# TEST_PLATFORM.net
KiCad netlist of a schematic drawn in Altium Designer
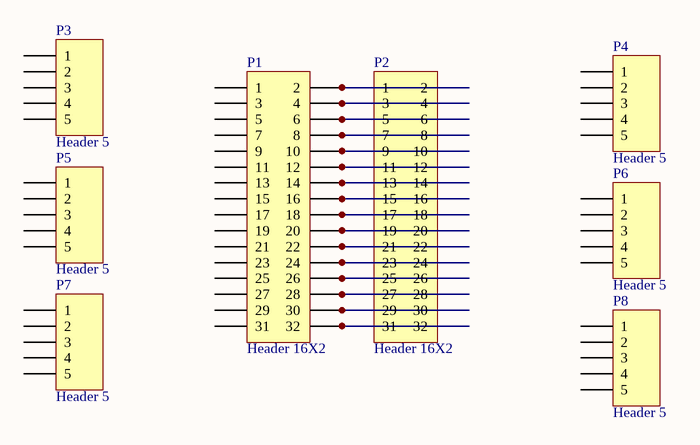
[diagram p0: TEST_PLATFORM.SchDoc]

(export (version "E")
  (design (tool "Eeschema 10.0.6"))
  (components
    (comp (ref "P1")
      (value "Header 16X2")
      (footprint "HDR2X16")
      (description "Header, 16-Pin, Dual row")
      (fields (field (name "PUBLISHER") "Altium Limited"))
      (libsource (lib "Miscellaneous Connectors") (part "Header 16X2"))
    )
    (comp (ref "P2")
      (value "Header 16X2")
      (footprint "HDR2X16")
      (description "Header, 16-Pin, Dual row")
      (fields (field (name "PUBLISHER") "Altium Limited"))
      (libsource (lib "Miscellaneous Connectors") (part "Header 16X2"))
    )
    (comp (ref "P3")
      (value "Header 5")
      (footprint "HDR1X5")
      (description "Header, 5-Pin")
      (fields (field (name "PUBLISHER") "Altium Limited"))
      (libsource (lib "Miscellaneous Connectors") (part "Header 5"))
    )
    (comp (ref "P4")
      (value "Header 5")
      (footprint "HDR1X5")
      (description "Header, 5-Pin")
      (fields (field (name "PUBLISHER") "Altium Limited"))
      (libsource (lib "Miscellaneous Connectors") (part "Header 5"))
    )
    (comp (ref "P5")
      (value "Header 5")
      (footprint "HDR1X5")
      (description "Header, 5-Pin")
      (fields (field (name "PUBLISHER") "Altium Limited"))
      (libsource (lib "Miscellaneous Connectors") (part "Header 5"))
    )
    (comp (ref "P6")
      (value "Header 5")
      (footprint "HDR1X5")
      (description "Header, 5-Pin")
      (fields (field (name "PUBLISHER") "Altium Limited"))
      (libsource (lib "Miscellaneous Connectors") (part "Header 5"))
    )
    (comp (ref "P7")
      (value "Header 5")
      (footprint "HDR1X5")
      (description "Header, 5-Pin")
      (fields (field (name "PUBLISHER") "Altium Limited"))
      (libsource (lib "Miscellaneous Connectors") (part "Header 5"))
    )
    (comp (ref "P8")
      (value "Header 5")
      (footprint "HDR1X5")
      (description "Header, 5-Pin")
      (fields (field (name "PUBLISHER") "Altium Limited"))
      (libsource (lib "Miscellaneous Connectors") (part "Header 5"))
    )
  )
  (nets
    (net (code "1") (name "Net-(P1-Pad2)") (class "Default")
      (node (ref "P1") (pin "2") (pinfunction "2_2") (pintype "passive"))
      (node (ref "P2") (pin "1") (pinfunction "1_1") (pintype "passive"))
      (node (ref "P2") (pin "2") (pinfunction "2_2") (pintype "passive"))
    )
    (net (code "2") (name "Net-(P1-Pad4)") (class "Default")
      (node (ref "P1") (pin "4") (pinfunction "4_4") (pintype "passive"))
      (node (ref "P2") (pin "3") (pinfunction "3_3") (pintype "passive"))
      (node (ref "P2") (pin "4") (pinfunction "4_4") (pintype "passive"))
    )
    (net (code "3") (name "Net-(P1-Pad6)") (class "Default")
      (node (ref "P1") (pin "6") (pinfunction "6_6") (pintype "passive"))
      (node (ref "P2") (pin "5") (pinfunction "5_5") (pintype "passive"))
      (node (ref "P2") (pin "6") (pinfunction "6_6") (pintype "passive"))
    )
    (net (code "4") (name "Net-(P1-Pad8)") (class "Default")
      (node (ref "P1") (pin "8") (pinfunction "8_8") (pintype "passive"))
      (node (ref "P2") (pin "7") (pinfunction "7_7") (pintype "passive"))
      (node (ref "P2") (pin "8") (pinfunction "8_8") (pintype "passive"))
    )
    (net (code "5") (name "Net-(P1-Pad10)") (class "Default")
      (node (ref "P1") (pin "10") (pinfunction "10_10") (pintype "passive"))
      (node (ref "P2") (pin "10") (pinfunction "10_10") (pintype "passive"))
      (node (ref "P2") (pin "9") (pinfunction "9_9") (pintype "passive"))
    )
    (net (code "6") (name "Net-(P1-Pad12)") (class "Default")
      (node (ref "P1") (pin "12") (pinfunction "12_12") (pintype "passive"))
      (node (ref "P2") (pin "11") (pinfunction "11_11") (pintype "passive"))
      (node (ref "P2") (pin "12") (pinfunction "12_12") (pintype "passive"))
    )
    (net (code "7") (name "Net-(P1-Pad14)") (class "Default")
      (node (ref "P1") (pin "14") (pinfunction "14_14") (pintype "passive"))
      (node (ref "P2") (pin "13") (pinfunction "13_13") (pintype "passive"))
      (node (ref "P2") (pin "14") (pinfunction "14_14") (pintype "passive"))
    )
    (net (code "8") (name "Net-(P1-Pad16)") (class "Default")
      (node (ref "P1") (pin "16") (pinfunction "16_16") (pintype "passive"))
      (node (ref "P2") (pin "15") (pinfunction "15_15") (pintype "passive"))
      (node (ref "P2") (pin "16") (pinfunction "16_16") (pintype "passive"))
    )
    (net (code "9") (name "Net-(P1-Pad18)") (class "Default")
      (node (ref "P1") (pin "18") (pinfunction "18_18") (pintype "passive"))
      (node (ref "P2") (pin "17") (pinfunction "17_17") (pintype "passive"))
      (node (ref "P2") (pin "18") (pinfunction "18_18") (pintype "passive"))
    )
    (net (code "10") (name "Net-(P1-Pad20)") (class "Default")
      (node (ref "P1") (pin "20") (pinfunction "20_20") (pintype "passive"))
      (node (ref "P2") (pin "19") (pinfunction "19_19") (pintype "passive"))
      (node (ref "P2") (pin "20") (pinfunction "20_20") (pintype "passive"))
    )
    (net (code "11") (name "Net-(P1-Pad22)") (class "Default")
      (node (ref "P1") (pin "22") (pinfunction "22_22") (pintype "passive"))
      (node (ref "P2") (pin "21") (pinfunction "21_21") (pintype "passive"))
      (node (ref "P2") (pin "22") (pinfunction "22_22") (pintype "passive"))
    )
    (net (code "12") (name "Net-(P1-Pad24)") (class "Default")
      (node (ref "P1") (pin "24") (pinfunction "24_24") (pintype "passive"))
      (node (ref "P2") (pin "23") (pinfunction "23_23") (pintype "passive"))
      (node (ref "P2") (pin "24") (pinfunction "24_24") (pintype "passive"))
    )
    (net (code "13") (name "Net-(P1-Pad26)") (class "Default")
      (node (ref "P1") (pin "26") (pinfunction "26_26") (pintype "passive"))
      (node (ref "P2") (pin "25") (pinfunction "25_25") (pintype "passive"))
      (node (ref "P2") (pin "26") (pinfunction "26_26") (pintype "passive"))
    )
    (net (code "14") (name "Net-(P1-Pad28)") (class "Default")
      (node (ref "P1") (pin "28") (pinfunction "28_28") (pintype "passive"))
      (node (ref "P2") (pin "27") (pinfunction "27_27") (pintype "passive"))
      (node (ref "P2") (pin "28") (pinfunction "28_28") (pintype "passive"))
    )
    (net (code "15") (name "Net-(P1-Pad30)") (class "Default")
      (node (ref "P1") (pin "30") (pinfunction "30_30") (pintype "passive"))
      (node (ref "P2") (pin "29") (pinfunction "29_29") (pintype "passive"))
      (node (ref "P2") (pin "30") (pinfunction "30_30") (pintype "passive"))
    )
    (net (code "16") (name "Net-(P1-Pad32)") (class "Default")
      (node (ref "P1") (pin "32") (pinfunction "32_32") (pintype "passive"))
      (node (ref "P2") (pin "31") (pinfunction "31_31") (pintype "passive"))
      (node (ref "P2") (pin "32") (pinfunction "32_32") (pintype "passive"))
    )
    (net (code "17") (name "unconnected-(P1-Pad1)") (class "Default")
      (node (ref "P1") (pin "1") (pinfunction "1_1") (pintype "passive"))
    )
    (net (code "18") (name "unconnected-(P1-Pad3)") (class "Default")
      (node (ref "P1") (pin "3") (pinfunction "3_3") (pintype "passive"))
    )
    (net (code "19") (name "unconnected-(P1-Pad5)") (class "Default")
      (node (ref "P1") (pin "5") (pinfunction "5_5") (pintype "passive"))
    )
    (net (code "20") (name "unconnected-(P1-Pad7)") (class "Default")
      (node (ref "P1") (pin "7") (pinfunction "7_7") (pintype "passive"))
    )
    (net (code "21") (name "unconnected-(P1-Pad9)") (class "Default")
      (node (ref "P1") (pin "9") (pinfunction "9_9") (pintype "passive"))
    )
    (net (code "22") (name "unconnected-(P1-Pad11)") (class "Default")
      (node (ref "P1") (pin "11") (pinfunction "11_11") (pintype "passive"))
    )
    (net (code "23") (name "unconnected-(P1-Pad13)") (class "Default")
      (node (ref "P1") (pin "13") (pinfunction "13_13") (pintype "passive"))
    )
    (net (code "24") (name "unconnected-(P1-Pad15)") (class "Default")
      (node (ref "P1") (pin "15") (pinfunction "15_15") (pintype "passive"))
    )
    (net (code "25") (name "unconnected-(P1-Pad17)") (class "Default")
      (node (ref "P1") (pin "17") (pinfunction "17_17") (pintype "passive"))
    )
    (net (code "26") (name "unconnected-(P1-Pad19)") (class "Default")
      (node (ref "P1") (pin "19") (pinfunction "19_19") (pintype "passive"))
    )
    (net (code "27") (name "unconnected-(P1-Pad21)") (class "Default")
      (node (ref "P1") (pin "21") (pinfunction "21_21") (pintype "passive"))
    )
    (net (code "28") (name "unconnected-(P1-Pad23)") (class "Default")
      (node (ref "P1") (pin "23") (pinfunction "23_23") (pintype "passive"))
    )
    (net (code "29") (name "unconnected-(P1-Pad25)") (class "Default")
      (node (ref "P1") (pin "25") (pinfunction "25_25") (pintype "passive"))
    )
    (net (code "30") (name "unconnected-(P1-Pad27)") (class "Default")
      (node (ref "P1") (pin "27") (pinfunction "27_27") (pintype "passive"))
    )
    (net (code "31") (name "unconnected-(P1-Pad29)") (class "Default")
      (node (ref "P1") (pin "29") (pinfunction "29_29") (pintype "passive"))
    )
    (net (code "32") (name "unconnected-(P1-Pad31)") (class "Default")
      (node (ref "P1") (pin "31") (pinfunction "31_31") (pintype "passive"))
    )
    (net (code "33") (name "unconnected-(P3-Pad1)") (class "Default")
      (node (ref "P3") (pin "1") (pinfunction "1_1") (pintype "passive"))
    )
    (net (code "34") (name "unconnected-(P3-Pad2)") (class "Default")
      (node (ref "P3") (pin "2") (pinfunction "2_2") (pintype "passive"))
    )
    (net (code "35") (name "unconnected-(P3-Pad3)") (class "Default")
      (node (ref "P3") (pin "3") (pinfunction "3_3") (pintype "passive"))
    )
    (net (code "36") (name "unconnected-(P3-Pad4)") (class "Default")
      (node (ref "P3") (pin "4") (pinfunction "4_4") (pintype "passive"))
    )
    (net (code "37") (name "unconnected-(P3-Pad5)") (class "Default")
      (node (ref "P3") (pin "5") (pinfunction "5_5") (pintype "passive"))
    )
    (net (code "38") (name "unconnected-(P4-Pad1)") (class "Default")
      (node (ref "P4") (pin "1") (pinfunction "1_1") (pintype "passive"))
    )
    (net (code "39") (name "unconnected-(P4-Pad2)") (class "Default")
      (node (ref "P4") (pin "2") (pinfunction "2_2") (pintype "passive"))
    )
    (net (code "40") (name "unconnected-(P4-Pad3)") (class "Default")
      (node (ref "P4") (pin "3") (pinfunction "3_3") (pintype "passive"))
    )
    (net (code "41") (name "unconnected-(P4-Pad4)") (class "Default")
      (node (ref "P4") (pin "4") (pinfunction "4_4") (pintype "passive"))
    )
    (net (code "42") (name "unconnected-(P4-Pad5)") (class "Default")
      (node (ref "P4") (pin "5") (pinfunction "5_5") (pintype "passive"))
    )
    (net (code "43") (name "unconnected-(P5-Pad1)") (class "Default")
      (node (ref "P5") (pin "1") (pinfunction "1_1") (pintype "passive"))
    )
    (net (code "44") (name "unconnected-(P5-Pad2)") (class "Default")
      (node (ref "P5") (pin "2") (pinfunction "2_2") (pintype "passive"))
    )
    (net (code "45") (name "unconnected-(P5-Pad3)") (class "Default")
      (node (ref "P5") (pin "3") (pinfunction "3_3") (pintype "passive"))
    )
    (net (code "46") (name "unconnected-(P5-Pad4)") (class "Default")
      (node (ref "P5") (pin "4") (pinfunction "4_4") (pintype "passive"))
    )
    (net (code "47") (name "unconnected-(P5-Pad5)") (class "Default")
      (node (ref "P5") (pin "5") (pinfunction "5_5") (pintype "passive"))
    )
    (net (code "48") (name "unconnected-(P6-Pad1)") (class "Default")
      (node (ref "P6") (pin "1") (pinfunction "1_1") (pintype "passive"))
    )
    (net (code "49") (name "unconnected-(P6-Pad2)") (class "Default")
      (node (ref "P6") (pin "2") (pinfunction "2_2") (pintype "passive"))
    )
    (net (code "50") (name "unconnected-(P6-Pad3)") (class "Default")
      (node (ref "P6") (pin "3") (pinfunction "3_3") (pintype "passive"))
    )
    (net (code "51") (name "unconnected-(P6-Pad4)") (class "Default")
      (node (ref "P6") (pin "4") (pinfunction "4_4") (pintype "passive"))
    )
    (net (code "52") (name "unconnected-(P6-Pad5)") (class "Default")
      (node (ref "P6") (pin "5") (pinfunction "5_5") (pintype "passive"))
    )
    (net (code "53") (name "unconnected-(P7-Pad1)") (class "Default")
      (node (ref "P7") (pin "1") (pinfunction "1_1") (pintype "passive"))
    )
    (net (code "54") (name "unconnected-(P7-Pad2)") (class "Default")
      (node (ref "P7") (pin "2") (pinfunction "2_2") (pintype "passive"))
    )
    (net (code "55") (name "unconnected-(P7-Pad3)") (class "Default")
      (node (ref "P7") (pin "3") (pinfunction "3_3") (pintype "passive"))
    )
    (net (code "56") (name "unconnected-(P7-Pad4)") (class "Default")
      (node (ref "P7") (pin "4") (pinfunction "4_4") (pintype "passive"))
    )
    (net (code "57") (name "unconnected-(P7-Pad5)") (class "Default")
      (node (ref "P7") (pin "5") (pinfunction "5_5") (pintype "passive"))
    )
    (net (code "58") (name "unconnected-(P8-Pad1)") (class "Default")
      (node (ref "P8") (pin "1") (pinfunction "1_1") (pintype "passive"))
    )
    (net (code "59") (name "unconnected-(P8-Pad2)") (class "Default")
      (node (ref "P8") (pin "2") (pinfunction "2_2") (pintype "passive"))
    )
    (net (code "60") (name "unconnected-(P8-Pad3)") (class "Default")
      (node (ref "P8") (pin "3") (pinfunction "3_3") (pintype "passive"))
    )
    (net (code "61") (name "unconnected-(P8-Pad4)") (class "Default")
      (node (ref "P8") (pin "4") (pinfunction "4_4") (pintype "passive"))
    )
    (net (code "62") (name "unconnected-(P8-Pad5)") (class "Default")
      (node (ref "P8") (pin "5") (pinfunction "5_5") (pintype "passive"))
    )
  )
)
